# uart.net
KiCad netlist of a schematic drawn in EAGLE
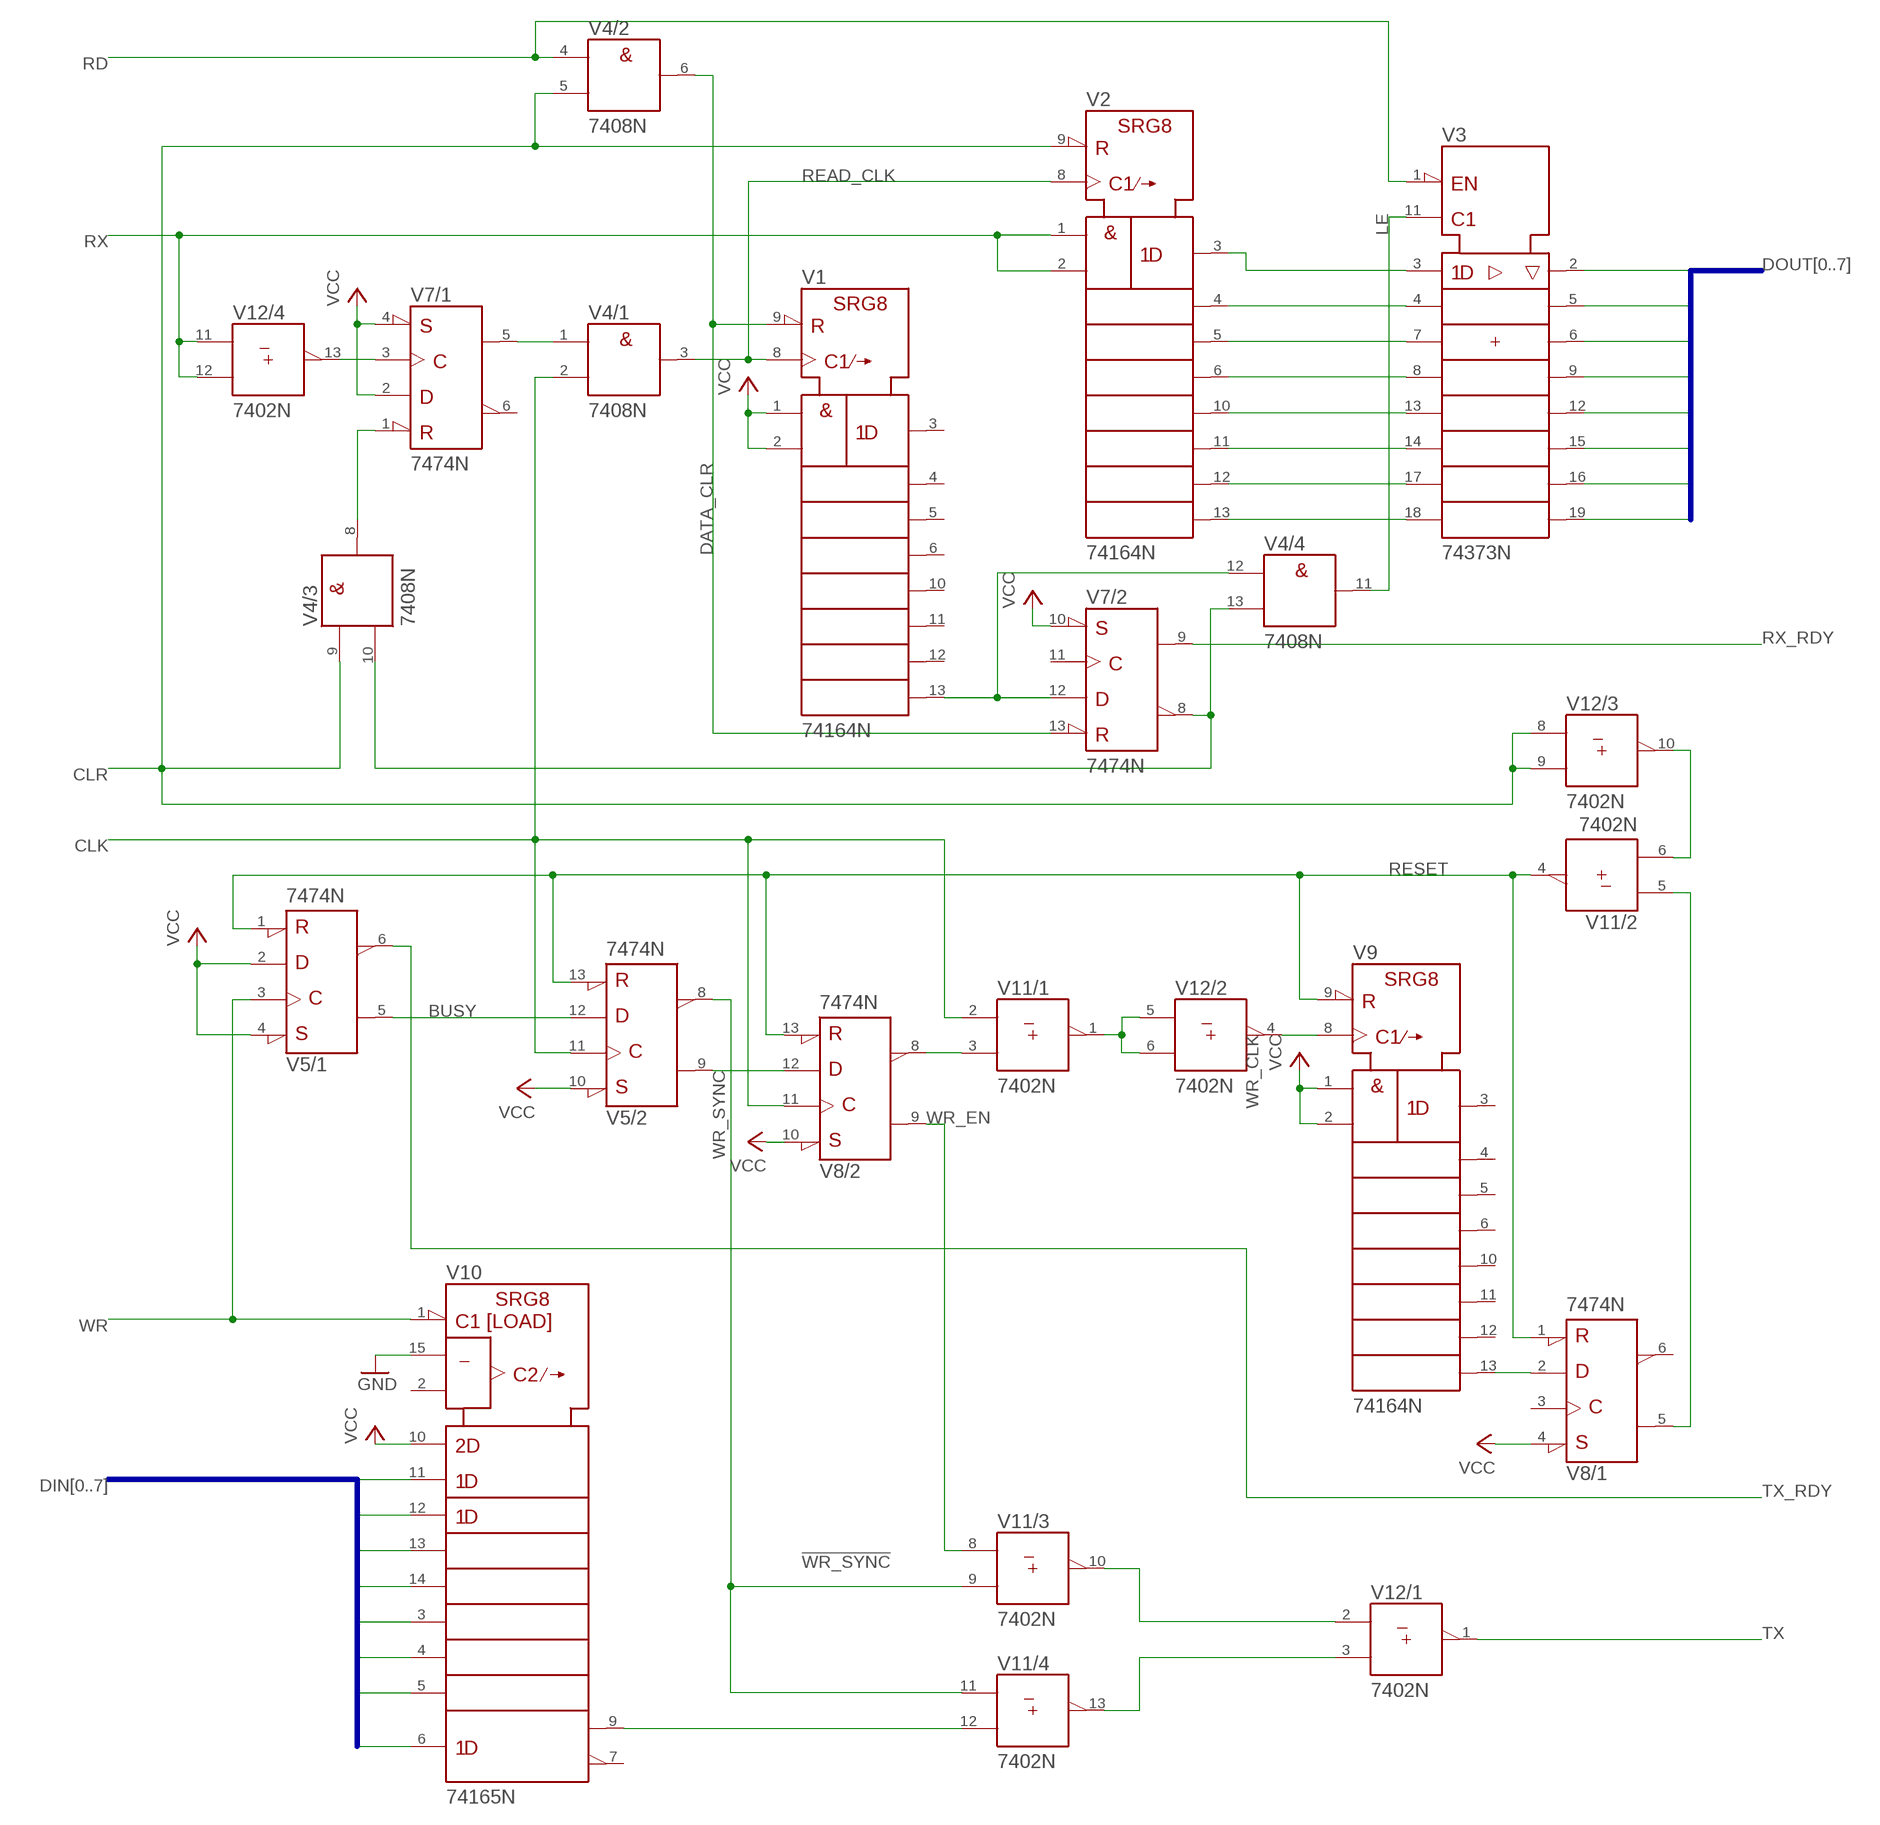
[diagram p0: schematic, sheet 1]

(export (version "E")
  (design (tool "Eeschema 10.0.6"))
  (components
    (comp (ref "V1")
      (value "74164N")
      (footprint "eagle-import:DIL14")
      (libsource (lib "eagle-import") (part "74164N"))
    )
    (comp (ref "V2")
      (value "74164N")
      (footprint "eagle-import:DIL14")
      (libsource (lib "eagle-import") (part "74164N"))
    )
    (comp (ref "V3")
      (value "74373N")
      (footprint "eagle-import:DIL20")
      (libsource (lib "eagle-import") (part "74373N"))
    )
    (comp (ref "V4")
      (value "7408N")
      (footprint "eagle-import:DIL14")
      (libsource (lib "eagle-import") (part "7408N"))
    )
    (comp (ref "V5")
      (value "7474N")
      (footprint "eagle-import:DIL14")
      (libsource (lib "eagle-import") (part "7474N"))
    )
    (comp (ref "V7")
      (value "7474N")
      (footprint "eagle-import:DIL14")
      (libsource (lib "eagle-import") (part "7474N"))
    )
    (comp (ref "V8")
      (value "7474N")
      (footprint "eagle-import:DIL14")
      (libsource (lib "eagle-import") (part "7474N"))
    )
    (comp (ref "V9")
      (value "74164N")
      (footprint "eagle-import:DIL14")
      (libsource (lib "eagle-import") (part "74164N"))
    )
    (comp (ref "V10")
      (value "74165N")
      (footprint "eagle-import:DIL16")
      (libsource (lib "eagle-import") (part "74165N"))
    )
    (comp (ref "V11")
      (value "7402N")
      (footprint "eagle-import:DIL14")
      (libsource (lib "eagle-import") (part "7402N"))
    )
    (comp (ref "V12")
      (value "7402N")
      (footprint "eagle-import:DIL14")
      (libsource (lib "eagle-import") (part "7402N"))
    )
  )
  (nets
    (net (code "17") (name "/BUSY") (class "Default")
      (node (ref "V5") (pin "12") (pinfunction "D_12") (pintype "input"))
      (node (ref "V5") (pin "5") (pinfunction "Q_5") (pintype "output"))
    )
    (net (code "18") (name "/CLK") (class "Default")
      (node (ref "V11") (pin "2") (pinfunction "A_2") (pintype "input"))
      (node (ref "V4") (pin "2") (pinfunction "B_2") (pintype "input"))
      (node (ref "V5") (pin "11") (pinfunction "CLK_11") (pintype "input"))
      (node (ref "V8") (pin "11") (pinfunction "CLK_11") (pintype "input"))
    )
    (net (code "19") (name "/CLR") (class "Default")
      (node (ref "V12") (pin "8") (pinfunction "A_8") (pintype "input"))
      (node (ref "V12") (pin "9") (pinfunction "B_9") (pintype "input"))
      (node (ref "V2") (pin "9") (pinfunction "~{CLR}_9") (pintype "input"))
      (node (ref "V4") (pin "5") (pinfunction "B_5") (pintype "input"))
      (node (ref "V4") (pin "9") (pinfunction "A_9") (pintype "input"))
    )
    (net (code "20") (name "/DATA_CLR") (class "Default")
      (node (ref "V1") (pin "9") (pinfunction "~{CLR}_9") (pintype "input"))
      (node (ref "V4") (pin "6") (pinfunction "Y_6") (pintype "output"))
      (node (ref "V7") (pin "13") (pinfunction "~{CLR}_13") (pintype "input"))
    )
    (net (code "23") (name "/LE") (class "Default")
      (node (ref "V3") (pin "11") (pinfunction "C_11") (pintype "input"))
      (node (ref "V4") (pin "11") (pinfunction "Y_11") (pintype "output"))
    )
    (net (code "24") (name "/RD") (class "Default")
      (node (ref "V3") (pin "1") (pinfunction "~{OC}_1") (pintype "input"))
      (node (ref "V4") (pin "4") (pinfunction "A_4") (pintype "input"))
    )
    (net (code "25") (name "/READ_CLK") (class "Default")
      (node (ref "V1") (pin "8") (pinfunction "CLK_8") (pintype "input"))
      (node (ref "V2") (pin "8") (pinfunction "CLK_8") (pintype "input"))
      (node (ref "V4") (pin "3") (pinfunction "Y_3") (pintype "output"))
    )
    (net (code "26") (name "/RESET") (class "Default")
      (node (ref "V11") (pin "4") (pinfunction "Y_4") (pintype "output"))
      (node (ref "V5") (pin "1") (pinfunction "~{CLR}_1") (pintype "input"))
      (node (ref "V5") (pin "13") (pinfunction "~{CLR}_13") (pintype "input"))
      (node (ref "V8") (pin "1") (pinfunction "~{CLR}_1") (pintype "input"))
      (node (ref "V8") (pin "13") (pinfunction "~{CLR}_13") (pintype "input"))
      (node (ref "V9") (pin "9") (pinfunction "~{CLR}_9") (pintype "input"))
    )
    (net (code "27") (name "/RX") (class "Default")
      (node (ref "V12") (pin "11") (pinfunction "A_11") (pintype "input"))
      (node (ref "V12") (pin "12") (pinfunction "B_12") (pintype "input"))
      (node (ref "V2") (pin "1") (pinfunction "A_1") (pintype "input"))
      (node (ref "V2") (pin "2") (pinfunction "B_2") (pintype "input"))
    )
    (net (code "28") (name "/RX_RDY") (class "Default")
      (node (ref "V7") (pin "9") (pinfunction "Q_9") (pintype "output"))
    )
    (net (code "29") (name "/TX") (class "Default")
      (node (ref "V12") (pin "1") (pinfunction "Y_1") (pintype "output"))
    )
    (net (code "30") (name "/TX_RDY") (class "Default")
      (node (ref "V5") (pin "6") (pinfunction "~{Q}_6") (pintype "output"))
    )
    (net (code "31") (name "/WR") (class "Default")
      (node (ref "V10") (pin "1") (pinfunction "SH/~{LD}_1") (pintype "input"))
      (node (ref "V5") (pin "3") (pinfunction "CLK_3") (pintype "input"))
    )
    (net (code "32") (name "/WR_CLK") (class "Default")
      (node (ref "V12") (pin "4") (pinfunction "Y_4") (pintype "output"))
      (node (ref "V9") (pin "8") (pinfunction "CLK_8") (pintype "input"))
    )
    (net (code "33") (name "/WR_EN") (class "Default")
      (node (ref "V11") (pin "8") (pinfunction "A_8") (pintype "input"))
      (node (ref "V8") (pin "9") (pinfunction "Q_9") (pintype "output"))
    )
    (net (code "34") (name "/WR_SYNC") (class "Default")
      (node (ref "V5") (pin "9") (pinfunction "Q_9") (pintype "output"))
      (node (ref "V8") (pin "12") (pinfunction "D_12") (pintype "input"))
    )
    (net (code "35") (name "/~{WR_SYNC}") (class "Default")
      (node (ref "V11") (pin "11") (pinfunction "A_11") (pintype "input"))
      (node (ref "V11") (pin "9") (pinfunction "B_9") (pintype "input"))
      (node (ref "V5") (pin "8") (pinfunction "~{Q}_8") (pintype "output"))
    )
    (net (code "36") (name "GND") (class "Default")
      (node (ref "V10") (pin "15") (pinfunction "CLK_INH_15") (pintype "input"))
    )
    (net (code "37") (name "Net-(V1C-QH)") (class "Default")
      (node (ref "V1") (pin "13") (pinfunction "QH_13") (pintype "output"))
      (node (ref "V4") (pin "12") (pinfunction "A_12") (pintype "input"))
      (node (ref "V7") (pin "12") (pinfunction "D_12") (pintype "input"))
    )
    (net (code "38") (name "Net-(V2C-QA)") (class "Default")
      (node (ref "V2") (pin "3") (pinfunction "QA_3") (pintype "output"))
      (node (ref "V3") (pin "3") (pinfunction "1D_3") (pintype "input"))
    )
    (net (code "39") (name "Net-(V2C-QB)") (class "Default")
      (node (ref "V2") (pin "4") (pinfunction "QB_4") (pintype "output"))
      (node (ref "V3") (pin "4") (pinfunction "2D_4") (pintype "input"))
    )
    (net (code "40") (name "Net-(V2C-QC)") (class "Default")
      (node (ref "V2") (pin "5") (pinfunction "QC_5") (pintype "output"))
      (node (ref "V3") (pin "7") (pinfunction "3D_7") (pintype "input"))
    )
    (net (code "41") (name "Net-(V2C-QD)") (class "Default")
      (node (ref "V2") (pin "6") (pinfunction "QD_6") (pintype "output"))
      (node (ref "V3") (pin "8") (pinfunction "4D_8") (pintype "input"))
    )
    (net (code "42") (name "Net-(V2C-QE)") (class "Default")
      (node (ref "V2") (pin "10") (pinfunction "QE_10") (pintype "output"))
      (node (ref "V3") (pin "13") (pinfunction "5D_13") (pintype "input"))
    )
    (net (code "43") (name "Net-(V2C-QF)") (class "Default")
      (node (ref "V2") (pin "11") (pinfunction "QF_11") (pintype "output"))
      (node (ref "V3") (pin "14") (pinfunction "6D_14") (pintype "input"))
    )
    (net (code "44") (name "Net-(V2C-QG)") (class "Default")
      (node (ref "V2") (pin "12") (pinfunction "QG_12") (pintype "output"))
      (node (ref "V3") (pin "17") (pinfunction "7D_17") (pintype "input"))
    )
    (net (code "45") (name "Net-(V2C-QH)") (class "Default")
      (node (ref "V2") (pin "13") (pinfunction "QH_13") (pintype "output"))
      (node (ref "V3") (pin "18") (pinfunction "8D_18") (pintype "input"))
    )
    (net (code "46") (name "Net-(V4C-A)") (class "Default")
      (node (ref "V4") (pin "1") (pinfunction "A_1") (pintype "input"))
      (node (ref "V7") (pin "5") (pinfunction "Q_5") (pintype "output"))
    )
    (net (code "47") (name "Net-(V4E-B)") (class "Default")
      (node (ref "V4") (pin "10") (pinfunction "B_10") (pintype "input"))
      (node (ref "V4") (pin "13") (pinfunction "B_13") (pintype "input"))
      (node (ref "V7") (pin "8") (pinfunction "~{Q}_8") (pintype "output"))
    )
    (net (code "48") (name "Net-(V4E-Y)") (class "Default")
      (node (ref "V4") (pin "8") (pinfunction "Y_8") (pintype "output"))
      (node (ref "V7") (pin "1") (pinfunction "~{CLR}_1") (pintype "input"))
    )
    (net (code "49") (name "Net-(V8C-D)") (class "Default")
      (node (ref "V8") (pin "2") (pinfunction "D_2") (pintype "input"))
      (node (ref "V9") (pin "13") (pinfunction "QH_13") (pintype "output"))
    )
    (net (code "50") (name "Net-(V10C-QH)") (class "Default")
      (node (ref "V10") (pin "9") (pinfunction "QH_9") (pintype "output"))
      (node (ref "V11") (pin "12") (pinfunction "B_12") (pintype "input"))
    )
    (net (code "51") (name "Net-(V11C-B)") (class "Default")
      (node (ref "V11") (pin "3") (pinfunction "B_3") (pintype "input"))
      (node (ref "V8") (pin "8") (pinfunction "~{Q}_8") (pintype "output"))
    )
    (net (code "52") (name "Net-(V11C-Y)") (class "Default")
      (node (ref "V11") (pin "1") (pinfunction "Y_1") (pintype "output"))
      (node (ref "V12") (pin "5") (pinfunction "A_5") (pintype "input"))
      (node (ref "V12") (pin "6") (pinfunction "B_6") (pintype "input"))
    )
    (net (code "53") (name "Net-(V11D-A)") (class "Default")
      (node (ref "V11") (pin "5") (pinfunction "A_5") (pintype "input"))
      (node (ref "V8") (pin "5") (pinfunction "Q_5") (pintype "output"))
    )
    (net (code "54") (name "Net-(V11D-B)") (class "Default")
      (node (ref "V11") (pin "6") (pinfunction "B_6") (pintype "input"))
      (node (ref "V12") (pin "10") (pinfunction "Y_10") (pintype "output"))
    )
    (net (code "55") (name "Net-(V11E-Y)") (class "Default")
      (node (ref "V11") (pin "10") (pinfunction "Y_10") (pintype "output"))
      (node (ref "V12") (pin "2") (pinfunction "A_2") (pintype "input"))
    )
    (net (code "56") (name "Net-(V11F-Y)") (class "Default")
      (node (ref "V11") (pin "13") (pinfunction "Y_13") (pintype "output"))
      (node (ref "V12") (pin "3") (pinfunction "B_3") (pintype "input"))
    )
    (net (code "57") (name "Net-(V12F-Y)") (class "Default")
      (node (ref "V12") (pin "13") (pinfunction "Y_13") (pintype "output"))
      (node (ref "V7") (pin "3") (pinfunction "CLK_3") (pintype "input"))
    )
    (net (code "58") (name "VCC") (class "Default")
      (node (ref "V1") (pin "1") (pinfunction "A_1") (pintype "input"))
      (node (ref "V1") (pin "2") (pinfunction "B_2") (pintype "input"))
      (node (ref "V10") (pin "10") (pinfunction "SER_10") (pintype "input"))
      (node (ref "V5") (pin "10") (pinfunction "~{PRE}_10") (pintype "input"))
      (node (ref "V5") (pin "2") (pinfunction "D_2") (pintype "input"))
      (node (ref "V5") (pin "4") (pinfunction "~{PRE}_4") (pintype "input"))
      (node (ref "V7") (pin "10") (pinfunction "~{PRE}_10") (pintype "input"))
      (node (ref "V7") (pin "2") (pinfunction "D_2") (pintype "input"))
      (node (ref "V7") (pin "4") (pinfunction "~{PRE}_4") (pintype "input"))
      (node (ref "V8") (pin "10") (pinfunction "~{PRE}_10") (pintype "input"))
      (node (ref "V8") (pin "4") (pinfunction "~{PRE}_4") (pintype "input"))
      (node (ref "V9") (pin "1") (pinfunction "A_1") (pintype "input"))
      (node (ref "V9") (pin "2") (pinfunction "B_2") (pintype "input"))
    )
    (net (code "59") (name "unconnected-(V1C-QA-Pad3)") (class "Default")
      (node (ref "V1") (pin "3") (pinfunction "QA_3") (pintype "output"))
    )
    (net (code "60") (name "unconnected-(V1C-QB-Pad4)") (class "Default")
      (node (ref "V1") (pin "4") (pinfunction "QB_4") (pintype "output"))
    )
    (net (code "61") (name "unconnected-(V1C-QC-Pad5)") (class "Default")
      (node (ref "V1") (pin "5") (pinfunction "QC_5") (pintype "output"))
    )
    (net (code "62") (name "unconnected-(V1C-QD-Pad6)") (class "Default")
      (node (ref "V1") (pin "6") (pinfunction "QD_6") (pintype "output"))
    )
    (net (code "63") (name "unconnected-(V1C-QE-Pad10)") (class "Default")
      (node (ref "V1") (pin "10") (pinfunction "QE_10") (pintype "output"))
    )
    (net (code "64") (name "unconnected-(V1C-QF-Pad11)") (class "Default")
      (node (ref "V1") (pin "11") (pinfunction "QF_11") (pintype "output"))
    )
    (net (code "65") (name "unconnected-(V1C-QG-Pad12)") (class "Default")
      (node (ref "V1") (pin "12") (pinfunction "QG_12") (pintype "output"))
    )
    (net (code "66") (name "unconnected-(V3C-1Q-Pad2)") (class "Default")
      (node (ref "V3") (pin "2") (pinfunction "1Q_2") (pintype "tri_state"))
    )
    (net (code "67") (name "unconnected-(V3C-2Q-Pad5)") (class "Default")
      (node (ref "V3") (pin "5") (pinfunction "2Q_5") (pintype "tri_state"))
    )
    (net (code "68") (name "unconnected-(V3C-3Q-Pad6)") (class "Default")
      (node (ref "V3") (pin "6") (pinfunction "3Q_6") (pintype "tri_state"))
    )
    (net (code "69") (name "unconnected-(V3C-4Q-Pad9)") (class "Default")
      (node (ref "V3") (pin "9") (pinfunction "4Q_9") (pintype "tri_state"))
    )
    (net (code "70") (name "unconnected-(V3C-5Q-Pad12)") (class "Default")
      (node (ref "V3") (pin "12") (pinfunction "5Q_12") (pintype "tri_state"))
    )
    (net (code "71") (name "unconnected-(V3C-6Q-Pad15)") (class "Default")
      (node (ref "V3") (pin "15") (pinfunction "6Q_15") (pintype "tri_state"))
    )
    (net (code "72") (name "unconnected-(V3C-7Q-Pad16)") (class "Default")
      (node (ref "V3") (pin "16") (pinfunction "7Q_16") (pintype "tri_state"))
    )
    (net (code "73") (name "unconnected-(V3C-8Q-Pad19)") (class "Default")
      (node (ref "V3") (pin "19") (pinfunction "8Q_19") (pintype "tri_state"))
    )
    (net (code "74") (name "unconnected-(V7C-~{Q}-Pad6)") (class "Default")
      (node (ref "V7") (pin "6") (pinfunction "~{Q}_6") (pintype "output"))
    )
    (net (code "75") (name "unconnected-(V7D-CLK-Pad11)") (class "Default")
      (node (ref "V7") (pin "11") (pinfunction "CLK_11") (pintype "input"))
    )
    (net (code "76") (name "unconnected-(V8C-CLK-Pad3)") (class "Default")
      (node (ref "V8") (pin "3") (pinfunction "CLK_3") (pintype "input"))
    )
    (net (code "77") (name "unconnected-(V8C-~{Q}-Pad6)") (class "Default")
      (node (ref "V8") (pin "6") (pinfunction "~{Q}_6") (pintype "output"))
    )
    (net (code "78") (name "unconnected-(V9C-QA-Pad3)") (class "Default")
      (node (ref "V9") (pin "3") (pinfunction "QA_3") (pintype "output"))
    )
    (net (code "79") (name "unconnected-(V9C-QB-Pad4)") (class "Default")
      (node (ref "V9") (pin "4") (pinfunction "QB_4") (pintype "output"))
    )
    (net (code "80") (name "unconnected-(V9C-QC-Pad5)") (class "Default")
      (node (ref "V9") (pin "5") (pinfunction "QC_5") (pintype "output"))
    )
    (net (code "81") (name "unconnected-(V9C-QD-Pad6)") (class "Default")
      (node (ref "V9") (pin "6") (pinfunction "QD_6") (pintype "output"))
    )
    (net (code "82") (name "unconnected-(V9C-QE-Pad10)") (class "Default")
      (node (ref "V9") (pin "10") (pinfunction "QE_10") (pintype "output"))
    )
    (net (code "83") (name "unconnected-(V9C-QF-Pad11)") (class "Default")
      (node (ref "V9") (pin "11") (pinfunction "QF_11") (pintype "output"))
    )
    (net (code "84") (name "unconnected-(V9C-QG-Pad12)") (class "Default")
      (node (ref "V9") (pin "12") (pinfunction "QG_12") (pintype "output"))
    )
    (net (code "85") (name "unconnected-(V10C-A-Pad11)") (class "Default")
      (node (ref "V10") (pin "11") (pinfunction "A_11") (pintype "input"))
    )
    (net (code "86") (name "unconnected-(V10C-B-Pad12)") (class "Default")
      (node (ref "V10") (pin "12") (pinfunction "B_12") (pintype "input"))
    )
    (net (code "87") (name "unconnected-(V10C-C-Pad13)") (class "Default")
      (node (ref "V10") (pin "13") (pinfunction "C_13") (pintype "input"))
    )
    (net (code "88") (name "unconnected-(V10C-CLK-Pad2)") (class "Default")
      (node (ref "V10") (pin "2") (pinfunction "CLK_2") (pintype "input"))
    )
    (net (code "89") (name "unconnected-(V10C-D-Pad14)") (class "Default")
      (node (ref "V10") (pin "14") (pinfunction "D_14") (pintype "input"))
    )
    (net (code "90") (name "unconnected-(V10C-E-Pad3)") (class "Default")
      (node (ref "V10") (pin "3") (pinfunction "E_3") (pintype "input"))
    )
    (net (code "91") (name "unconnected-(V10C-F-Pad4)") (class "Default")
      (node (ref "V10") (pin "4") (pinfunction "F_4") (pintype "input"))
    )
    (net (code "92") (name "unconnected-(V10C-G-Pad5)") (class "Default")
      (node (ref "V10") (pin "5") (pinfunction "G_5") (pintype "input"))
    )
    (net (code "93") (name "unconnected-(V10C-H-Pad6)") (class "Default")
      (node (ref "V10") (pin "6") (pinfunction "H_6") (pintype "input"))
    )
    (net (code "94") (name "unconnected-(V10C-~{QH}-Pad7)") (class "Default")
      (node (ref "V10") (pin "7") (pinfunction "~{QH}_7") (pintype "output"))
    )
  )
)
